# POWER_3_3V_6A.net
KiCad netlist of a schematic drawn in Altium Designer
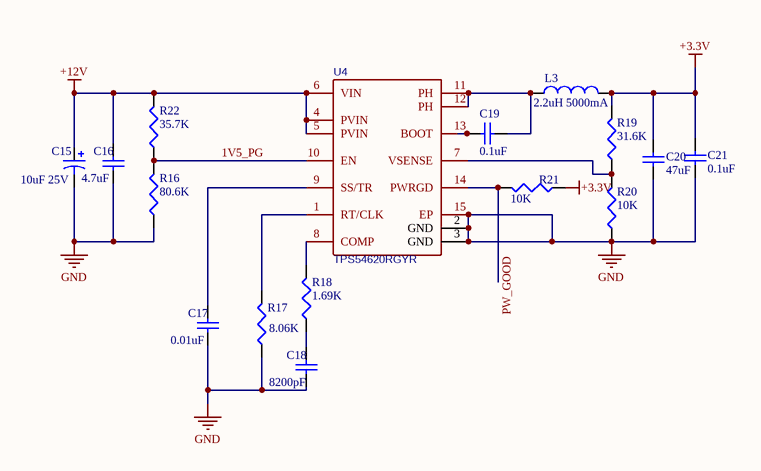
[diagram p0: POWER_3.3V_6A.SchDoc]

(export (version "E")
  (design (tool "Eeschema 10.0.6"))
  (components
    (comp (ref "C15")
      (value "10uF 25V")
      (footprint "47UF_16V")
      (description "Polarized Capacitor (Radial)")
      (fields (field (name "Comment") "Cap Pol1") (field (name "PUBLISHER") "Altium Limited"))
      (libsource (lib "Miscellaneous Devices") (part "Cap Pol1"))
    )
    (comp (ref "C16")
      (value "4.7uF")
      (footprint "C1210")
      (description "Capacitor (Semiconductor SIM Model)")
      (fields (field (name "Comment") "Cap Semi") (field (name "PUBLISHER") "Altium Limited"))
      (libsource (lib "Miscellaneous Devices") (part "Cap Semi"))
    )
    (comp (ref "C17")
      (value "0.01uF")
      (footprint "C1210")
      (description "Capacitor (Semiconductor SIM Model)")
      (fields (field (name "Comment") "Cap Semi") (field (name "PUBLISHER") "Altium Limited"))
      (libsource (lib "Miscellaneous Devices") (part "Cap Semi"))
    )
    (comp (ref "C18")
      (value "8200pF")
      (footprint "C1210")
      (description "Capacitor (Semiconductor SIM Model)")
      (fields (field (name "Comment") "Cap Semi") (field (name "PUBLISHER") "Altium Limited"))
      (libsource (lib "Miscellaneous Devices") (part "Cap Semi"))
    )
    (comp (ref "C19")
      (value "0.1uF")
      (footprint "C1210")
      (description "Capacitor (Semiconductor SIM Model)")
      (fields (field (name "Comment") "Cap Semi") (field (name "PUBLISHER") "Altium Limited"))
      (libsource (lib "Miscellaneous Devices") (part "Cap Semi"))
    )
    (comp (ref "C20")
      (value "47uF")
      (footprint "C1210")
      (description "Capacitor (Semiconductor SIM Model)")
      (fields (field (name "Comment") "Cap Semi") (field (name "PUBLISHER") "Altium Limited"))
      (libsource (lib "Miscellaneous Devices") (part "Cap Semi"))
    )
    (comp (ref "C21")
      (value "0.1uF")
      (footprint "C1210")
      (description "Capacitor (Semiconductor SIM Model)")
      (fields (field (name "Comment") "Cap Semi") (field (name "PUBLISHER") "Altium Limited"))
      (libsource (lib "Miscellaneous Devices") (part "Cap Semi"))
    )
    (comp (ref "L3")
      (value "2.2uH 5000mA")
      (footprint "IND-SMD_L5.5-W5.2")
      (description "Inductor")
      (fields (field (name "PUBLISHER") "Altium Limited"))
      (libsource (lib "Miscellaneous Devices") (part "Inductor"))
    )
    (comp (ref "R16")
      (value "80.6K")
      (footprint "J1-0603")
      (description "Resistor")
      (fields (field (name "Comment") "Res3") (field (name "PUBLISHER") "Altium Limited"))
      (libsource (lib "Miscellaneous Devices") (part "Res3"))
    )
    (comp (ref "R17")
      (value "8.06K")
      (footprint "J1-0603")
      (description "Resistor")
      (fields (field (name "Comment") "Res3") (field (name "PUBLISHER") "Altium Limited"))
      (libsource (lib "Miscellaneous Devices") (part "Res3"))
    )
    (comp (ref "R18")
      (value "1.69K")
      (footprint "J1-0603")
      (description "Resistor")
      (fields (field (name "Comment") "Res3") (field (name "PUBLISHER") "Altium Limited"))
      (libsource (lib "Miscellaneous Devices") (part "Res3"))
    )
    (comp (ref "R19")
      (value "31.6K")
      (footprint "J1-0603")
      (description "Resistor")
      (fields (field (name "Comment") "Res3") (field (name "PUBLISHER") "Altium Limited"))
      (libsource (lib "Miscellaneous Devices") (part "Res3"))
    )
    (comp (ref "R20")
      (value "10K")
      (footprint "J1-0603")
      (description "Resistor")
      (fields (field (name "Comment") "Res3") (field (name "PUBLISHER") "Altium Limited"))
      (libsource (lib "Miscellaneous Devices") (part "Res3"))
    )
    (comp (ref "R21")
      (value "10K")
      (footprint "J1-0603")
      (description "Resistor")
      (fields (field (name "Comment") "Res3") (field (name "PUBLISHER") "Altium Limited"))
      (libsource (lib "Miscellaneous Devices") (part "Res3"))
    )
    (comp (ref "R22")
      (value "35.7K")
      (footprint "J1-0603")
      (description "Resistor")
      (fields (field (name "Comment") "Res3") (field (name "PUBLISHER") "Altium Limited"))
      (libsource (lib "Miscellaneous Devices") (part "Res3"))
    )
    (comp (ref "U4")
      (value "TPS54620RGYR")
      (footprint "VQFN-14_L3.5-W3.5-P0.50-TL-EP_TPS54622RHLT")
      (fields (field (name "BOM_SUPPLIER PART") "C29438"))
      (libsource (lib "power_chip") (part "TPS54620RGYR"))
    )
  )
  (nets
    (net (code "1") (name "+3.3V") (class "Default")
      (node (ref "C20") (pin "1") (pinfunction "1_1") (pintype "passive"))
      (node (ref "C21") (pin "1") (pinfunction "1_1") (pintype "passive"))
      (node (ref "L3") (pin "2") (pinfunction "2_2") (pintype "passive"))
      (node (ref "R19") (pin "2") (pinfunction "2_2") (pintype "passive"))
      (node (ref "R21") (pin "1") (pinfunction "1_1") (pintype "passive"))
    )
    (net (code "2") (name "+12V") (class "Default")
      (node (ref "C15") (pin "1") (pinfunction "1_1") (pintype "passive"))
      (node (ref "C16") (pin "2") (pinfunction "2_2") (pintype "passive"))
      (node (ref "R22") (pin "2") (pinfunction "2_2") (pintype "passive"))
      (node (ref "U4") (pin "4") (pinfunction "PVIN_4") (pintype "passive"))
      (node (ref "U4") (pin "5") (pinfunction "PVIN_5") (pintype "passive"))
      (node (ref "U4") (pin "6") (pinfunction "VIN_6") (pintype "passive"))
    )
    (net (code "3") (name "/1V5_PG") (class "Default")
      (node (ref "R16") (pin "2") (pinfunction "2_2") (pintype "passive"))
      (node (ref "R22") (pin "1") (pinfunction "1_1") (pintype "passive"))
      (node (ref "U4") (pin "10") (pinfunction "EN_10") (pintype "passive"))
    )
    (net (code "4") (name "/PW_GOOD") (class "Default")
      (node (ref "R21") (pin "2") (pinfunction "2_2") (pintype "passive"))
      (node (ref "U4") (pin "14") (pinfunction "PWRGD_14") (pintype "passive"))
    )
    (net (code "5") (name "GND") (class "Default")
      (node (ref "C15") (pin "2") (pinfunction "2_2") (pintype "passive"))
      (node (ref "C16") (pin "1") (pinfunction "1_1") (pintype "passive"))
      (node (ref "C17") (pin "1") (pinfunction "1_1") (pintype "passive"))
      (node (ref "C18") (pin "1") (pinfunction "1_1") (pintype "passive"))
      (node (ref "C20") (pin "2") (pinfunction "2_2") (pintype "passive"))
      (node (ref "C21") (pin "2") (pinfunction "2_2") (pintype "passive"))
      (node (ref "R16") (pin "1") (pinfunction "1_1") (pintype "passive"))
      (node (ref "R17") (pin "1") (pinfunction "1_1") (pintype "passive"))
      (node (ref "R20") (pin "1") (pinfunction "1_1") (pintype "passive"))
      (node (ref "U4") (pin "15") (pinfunction "EP_15") (pintype "passive"))
      (node (ref "U4") (pin "2") (pinfunction "GND_2") (pintype "passive"))
      (node (ref "U4") (pin "3") (pinfunction "GND_3") (pintype "passive"))
    )
    (net (code "6") (name "Net-(C18-Pad2)") (class "Default")
      (node (ref "C18") (pin "2") (pinfunction "2_2") (pintype "passive"))
      (node (ref "R18") (pin "1") (pinfunction "1_1") (pintype "passive"))
    )
    (net (code "7") (name "Net-(C19-Pad1)") (class "Default")
      (node (ref "C19") (pin "1") (pinfunction "1_1") (pintype "passive"))
      (node (ref "L3") (pin "1") (pinfunction "1_1") (pintype "passive"))
      (node (ref "U4") (pin "11") (pinfunction "PH_11") (pintype "passive"))
      (node (ref "U4") (pin "12") (pinfunction "PH_12") (pintype "passive"))
    )
    (net (code "8") (name "Net-(U4-BOOT)") (class "Default")
      (node (ref "C19") (pin "2") (pinfunction "2_2") (pintype "passive"))
      (node (ref "U4") (pin "13") (pinfunction "BOOT_13") (pintype "passive"))
    )
    (net (code "9") (name "Net-(U4-COMP)") (class "Default")
      (node (ref "R18") (pin "2") (pinfunction "2_2") (pintype "passive"))
      (node (ref "U4") (pin "8") (pinfunction "COMP_8") (pintype "passive"))
    )
    (net (code "10") (name "Net-(U4-RT{slash}CLK)") (class "Default")
      (node (ref "R17") (pin "2") (pinfunction "2_2") (pintype "passive"))
      (node (ref "U4") (pin "1") (pinfunction "RT/CLK_1") (pintype "passive"))
    )
    (net (code "11") (name "Net-(U4-SS{slash}TR)") (class "Default")
      (node (ref "C17") (pin "2") (pinfunction "2_2") (pintype "passive"))
      (node (ref "U4") (pin "9") (pinfunction "SS/TR_9") (pintype "passive"))
    )
    (net (code "12") (name "Net-(U4-VSENSE)") (class "Default")
      (node (ref "R19") (pin "1") (pinfunction "1_1") (pintype "passive"))
      (node (ref "R20") (pin "2") (pinfunction "2_2") (pintype "passive"))
      (node (ref "U4") (pin "7") (pinfunction "VSENSE_7") (pintype "passive"))
    )
  )
)
